# adc.net
KiCad netlist of a schematic drawn in EAGLE
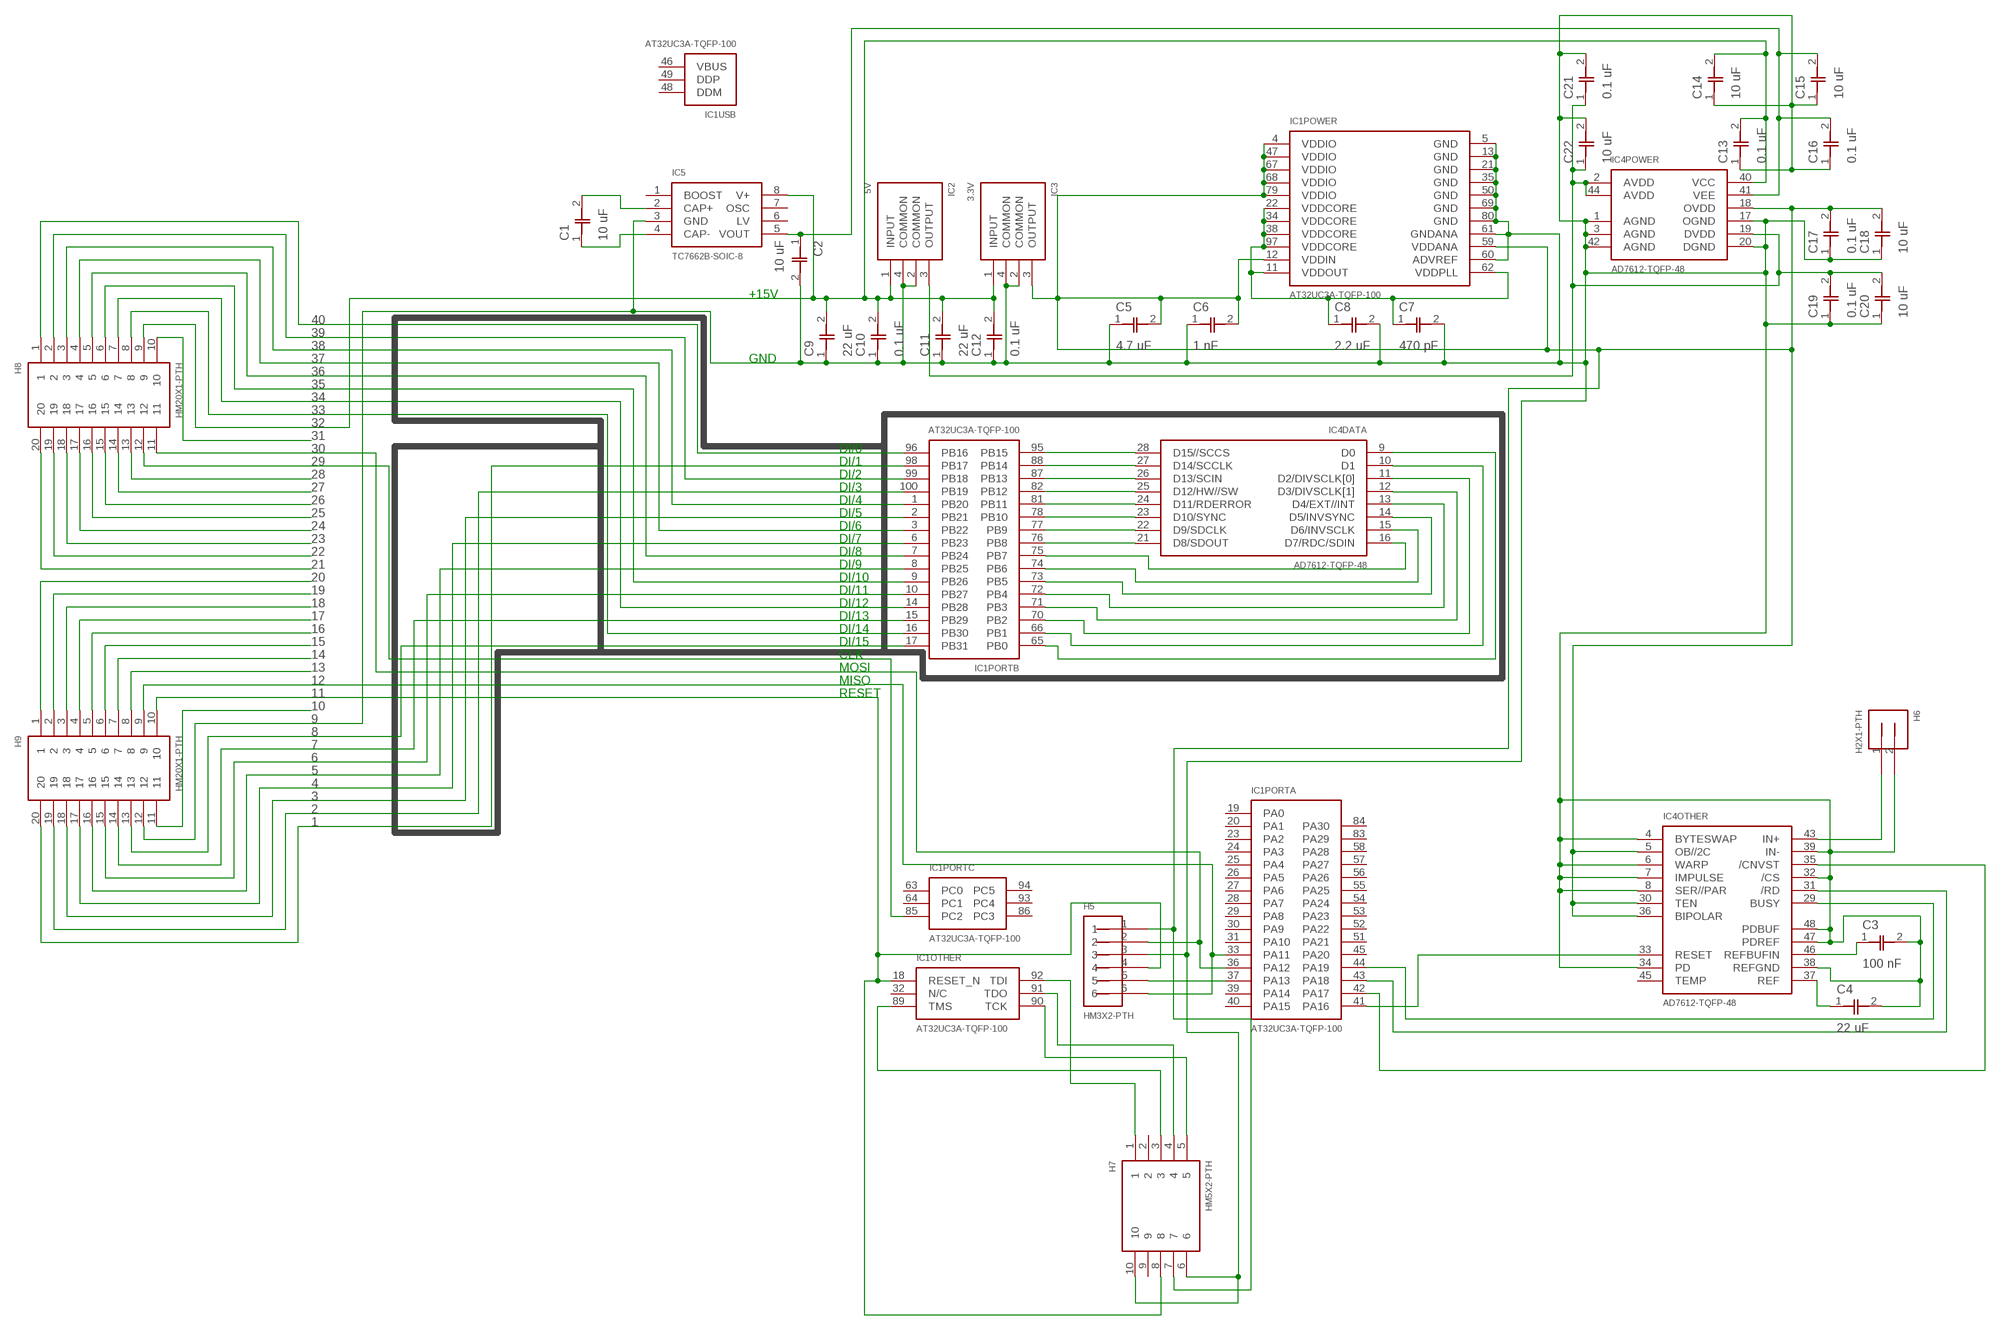
[diagram p0: schematic, sheet 1]

(export (version "E")
  (design (tool "Eeschema 10.0.6"))
  (components
    (comp (ref "C1")
      (value "10 uF")
      (footprint "eagle-import:CAP-0805")
      (libsource (lib "eagle-import") (part "CAP-0805"))
    )
    (comp (ref "C2")
      (value "10 uF")
      (footprint "eagle-import:CAP-0805")
      (libsource (lib "eagle-import") (part "CAP-0805"))
    )
    (comp (ref "C3")
      (value "100 nF")
      (footprint "eagle-import:CAP-0603")
      (libsource (lib "eagle-import") (part "july13b_CAP-0603"))
    )
    (comp (ref "C4")
      (value "22 uF")
      (footprint "eagle-import:CAP-0805")
      (libsource (lib "eagle-import") (part "CAP-0805"))
    )
    (comp (ref "C5")
      (value "4.7 uF")
      (footprint "eagle-import:CAP-0603")
      (libsource (lib "eagle-import") (part "july13b_CAP-0603"))
    )
    (comp (ref "C6")
      (value "1 nF")
      (footprint "eagle-import:CAP-0603")
      (libsource (lib "eagle-import") (part "july13b_CAP-0603"))
    )
    (comp (ref "C7")
      (value "470 pF")
      (footprint "eagle-import:CAP-0603")
      (libsource (lib "eagle-import") (part "july13b_CAP-0603"))
    )
    (comp (ref "C8")
      (value "2.2 uF")
      (footprint "eagle-import:CAP-0603")
      (libsource (lib "eagle-import") (part "july13b_CAP-0603"))
    )
    (comp (ref "C9")
      (value "22 uF")
      (footprint "eagle-import:CAP-0805")
      (libsource (lib "eagle-import") (part "CAP-0805"))
    )
    (comp (ref "C10")
      (value "0.1 uF")
      (footprint "eagle-import:CAP-0603")
      (libsource (lib "eagle-import") (part "july13b_CAP-0603"))
    )
    (comp (ref "C11")
      (value "22 uF")
      (footprint "eagle-import:CAP-0805")
      (libsource (lib "eagle-import") (part "CAP-0805"))
    )
    (comp (ref "C12")
      (value "0.1 uF")
      (footprint "eagle-import:CAP-0603")
      (libsource (lib "eagle-import") (part "july13b_CAP-0603"))
    )
    (comp (ref "C13")
      (value "0.1 uF")
      (footprint "eagle-import:CAP-0603")
      (libsource (lib "eagle-import") (part "july13b_CAP-0603"))
    )
    (comp (ref "C14")
      (value "10 uF")
      (footprint "eagle-import:CAP-0805")
      (libsource (lib "eagle-import") (part "CAP-0805"))
    )
    (comp (ref "C15")
      (value "10 uF")
      (footprint "eagle-import:CAP-0805")
      (libsource (lib "eagle-import") (part "CAP-0805"))
    )
    (comp (ref "C16")
      (value "0.1 uF")
      (footprint "eagle-import:CAP-0603")
      (libsource (lib "eagle-import") (part "july13b_CAP-0603"))
    )
    (comp (ref "C17")
      (value "0.1 uF")
      (footprint "eagle-import:CAP-0603")
      (libsource (lib "eagle-import") (part "july13b_CAP-0603"))
    )
    (comp (ref "C18")
      (value "10 uF")
      (footprint "eagle-import:CAP-0603")
      (libsource (lib "eagle-import") (part "july13b_CAP-0603"))
    )
    (comp (ref "C19")
      (value "0.1 uF")
      (footprint "eagle-import:CAP-0603")
      (libsource (lib "eagle-import") (part "july13b_CAP-0603"))
    )
    (comp (ref "C20")
      (value "10 uF")
      (footprint "eagle-import:CAP-0603")
      (libsource (lib "eagle-import") (part "july13b_CAP-0603"))
    )
    (comp (ref "C21")
      (value "0.1 uF")
      (footprint "eagle-import:CAP-0603")
      (libsource (lib "eagle-import") (part "july13b_CAP-0603"))
    )
    (comp (ref "C22")
      (value "10 uF")
      (footprint "eagle-import:CAP-0603")
      (libsource (lib "eagle-import") (part "july13b_CAP-0603"))
    )
    (comp (ref "H5")
      (value "HM3X2-PTH")
      (footprint "eagle-import:HM3X2-PTH")
      (libsource (lib "eagle-import") (part "HM3X2-PTH"))
    )
    (comp (ref "H6")
      (value "H2X1-PTH")
      (footprint "eagle-import:HM2X1-PTH")
      (libsource (lib "eagle-import") (part "H2X1-PTH"))
    )
    (comp (ref "H7")
      (value "HM5X2-PTH")
      (footprint "eagle-import:HM5X2-PTH")
      (libsource (lib "eagle-import") (part "HM5X2-PTH"))
    )
    (comp (ref "H8")
      (value "HM20X1-PTH")
      (footprint "eagle-import:HM20X1-PTH")
      (libsource (lib "eagle-import") (part "HM20X1-PTH"))
    )
    (comp (ref "H9")
      (value "HM20X1-PTH")
      (footprint "eagle-import:HM20X1-PTH")
      (libsource (lib "eagle-import") (part "HM20X1-PTH"))
    )
    (comp (ref "IC1")
      (value "AT32UC3A-TQFP-100")
      (footprint "eagle-import:TQFP-100")
      (libsource (lib "eagle-import") (part "AT32UC3A-TQFP-100"))
    )
    (comp (ref "IC2")
      (value "5V")
      (footprint "eagle-import:SOT-223-4")
      (libsource (lib "eagle-import") (part "UA78M-SOT-223-4"))
    )
    (comp (ref "IC3")
      (value "3.3V")
      (footprint "eagle-import:SOT-223-4")
      (libsource (lib "eagle-import") (part "UA78M-SOT-223-4"))
    )
    (comp (ref "IC4")
      (value "AD7612-TQFP-48")
      (footprint "eagle-import:LQFP-48")
      (libsource (lib "eagle-import") (part "AD7612-TQFP-48"))
    )
    (comp (ref "IC5")
      (value "TC7662B-SOIC-8")
      (footprint "eagle-import:SOIC-8")
      (libsource (lib "eagle-import") (part "TC7662B-SOIC-8"))
    )
  )
  (nets
    (net (code "1") (name "/1") (class "Default")
      (node (ref "H9") (pin "20") (pinfunction "20_20") (pintype "bidirectional"))
      (node (ref "IC1") (pin "98") (pinfunction "PB17_98") (pintype "bidirectional"))
    )
    (net (code "2") (name "/2") (class "Default")
      (node (ref "H9") (pin "19") (pinfunction "19_19") (pintype "bidirectional"))
      (node (ref "IC1") (pin "100") (pinfunction "PB19_100") (pintype "bidirectional"))
    )
    (net (code "3") (name "/3") (class "Default")
      (node (ref "H9") (pin "18") (pinfunction "18_18") (pintype "bidirectional"))
      (node (ref "IC1") (pin "2") (pinfunction "PB21_2") (pintype "bidirectional"))
    )
    (net (code "4") (name "/4") (class "Default")
      (node (ref "H9") (pin "17") (pinfunction "17_17") (pintype "bidirectional"))
      (node (ref "IC1") (pin "6") (pinfunction "PB23_6") (pintype "bidirectional"))
    )
    (net (code "5") (name "/5") (class "Default")
      (node (ref "H9") (pin "16") (pinfunction "16_16") (pintype "bidirectional"))
      (node (ref "IC1") (pin "8") (pinfunction "PB25_8") (pintype "bidirectional"))
    )
    (net (code "6") (name "/6") (class "Default")
      (node (ref "H9") (pin "15") (pinfunction "15_15") (pintype "bidirectional"))
      (node (ref "IC1") (pin "10") (pinfunction "PB27_10") (pintype "bidirectional"))
    )
    (net (code "7") (name "/7") (class "Default")
      (node (ref "H9") (pin "14") (pinfunction "14_14") (pintype "bidirectional"))
      (node (ref "IC1") (pin "15") (pinfunction "PB29_15") (pintype "bidirectional"))
    )
    (net (code "8") (name "/8") (class "Default")
      (node (ref "H9") (pin "13") (pinfunction "13_13") (pintype "bidirectional"))
      (node (ref "IC1") (pin "17") (pinfunction "PB31_17") (pintype "bidirectional"))
    )
    (net (code "9") (name "/9") (class "Default")
      (node (ref "C10") (pin "1") (pinfunction "1_1") (pintype "passive"))
      (node (ref "C11") (pin "1") (pinfunction "1_1") (pintype "passive"))
      (node (ref "C12") (pin "1") (pinfunction "1_1") (pintype "passive"))
      (node (ref "C13") (pin "1") (pinfunction "1_1") (pintype "passive"))
      (node (ref "C14") (pin "1") (pinfunction "1_1") (pintype "passive"))
      (node (ref "C15") (pin "1") (pinfunction "1_1") (pintype "passive"))
      (node (ref "C16") (pin "1") (pinfunction "1_1") (pintype "passive"))
      (node (ref "C17") (pin "1") (pinfunction "1_1") (pintype "passive"))
      (node (ref "C18") (pin "1") (pinfunction "1_1") (pintype "passive"))
      (node (ref "C19") (pin "1") (pinfunction "1_1") (pintype "passive"))
      (node (ref "C2") (pin "2") (pinfunction "2_2") (pintype "passive"))
      (node (ref "C20") (pin "1") (pinfunction "1_1") (pintype "passive"))
      (node (ref "C21") (pin "2") (pinfunction "2_2") (pintype "passive"))
      (node (ref "C22") (pin "2") (pinfunction "2_2") (pintype "passive"))
      (node (ref "C3") (pin "2") (pinfunction "2_2") (pintype "passive"))
      (node (ref "C4") (pin "2") (pinfunction "2_2") (pintype "passive"))
      (node (ref "C5") (pin "1") (pinfunction "1_1") (pintype "passive"))
      (node (ref "C6") (pin "1") (pinfunction "1_1") (pintype "passive"))
      (node (ref "C7") (pin "2") (pinfunction "2_2") (pintype "passive"))
      (node (ref "C8") (pin "2") (pinfunction "2_2") (pintype "passive"))
      (node (ref "C9") (pin "1") (pinfunction "1_1") (pintype "passive"))
      (node (ref "H5") (pin "3") (pinfunction "3_3") (pintype "passive"))
      (node (ref "H6") (pin "2") (pinfunction "2_2") (pintype "passive"))
      (node (ref "H7") (pin "10") (pinfunction "10_10") (pintype "passive"))
      (node (ref "H7") (pin "6") (pinfunction "6_6") (pintype "passive"))
      (node (ref "H9") (pin "12") (pinfunction "12_12") (pintype "bidirectional"))
      (node (ref "IC1") (pin "13") (pinfunction "GND_13") (pintype "power_in"))
      (node (ref "IC1") (pin "21") (pinfunction "GND_21") (pintype "power_in"))
      (node (ref "IC1") (pin "35") (pinfunction "GND_35") (pintype "power_in"))
      (node (ref "IC1") (pin "5") (pinfunction "GND_5") (pintype "power_in"))
      (node (ref "IC1") (pin "50") (pinfunction "GND_50") (pintype "power_in"))
      (node (ref "IC1") (pin "60") (pinfunction "ADVREF_60") (pintype "bidirectional"))
      (node (ref "IC1") (pin "61") (pinfunction "GNDANA_61") (pintype "power_in"))
      (node (ref "IC1") (pin "69") (pinfunction "GND_69") (pintype "power_in"))
      (node (ref "IC1") (pin "80") (pinfunction "GND_80") (pintype "power_in"))
      (node (ref "IC2") (pin "2") (pinfunction "COMMON_2") (pintype "power_in"))
      (node (ref "IC2") (pin "4") (pinfunction "COMMON_4") (pintype "power_in"))
      (node (ref "IC3") (pin "2") (pinfunction "COMMON_2") (pintype "power_in"))
      (node (ref "IC3") (pin "4") (pinfunction "COMMON_4") (pintype "power_in"))
      (node (ref "IC4") (pin "1") (pinfunction "AGND_1") (pintype "power_in"))
      (node (ref "IC4") (pin "17") (pinfunction "OGND_17") (pintype "power_in"))
      (node (ref "IC4") (pin "20") (pinfunction "DGND_20") (pintype "power_in"))
      (node (ref "IC4") (pin "3") (pinfunction "AGND_3") (pintype "power_in"))
      (node (ref "IC4") (pin "32") (pinfunction "/CS_32") (pintype "input"))
      (node (ref "IC4") (pin "34") (pinfunction "PD_34") (pintype "input"))
      (node (ref "IC4") (pin "38") (pinfunction "REFGND_38") (pintype "input"))
      (node (ref "IC4") (pin "39") (pinfunction "IN-_39") (pintype "input"))
      (node (ref "IC4") (pin "4") (pinfunction "BYTESWAP_4") (pintype "input"))
      (node (ref "IC4") (pin "42") (pinfunction "AGND_42") (pintype "power_in"))
      (node (ref "IC4") (pin "47") (pinfunction "PDREF_47") (pintype "input"))
      (node (ref "IC4") (pin "48") (pinfunction "PDBUF_48") (pintype "input"))
      (node (ref "IC4") (pin "6") (pinfunction "WARP_6") (pintype "input"))
      (node (ref "IC4") (pin "7") (pinfunction "IMPULSE_7") (pintype "input"))
      (node (ref "IC4") (pin "8") (pinfunction "SER//PAR_8") (pintype "input"))
      (node (ref "IC5") (pin "3") (pinfunction "GND_3") (pintype "power_in"))
    )
    (net (code "10") (name "/10") (class "Default")
      (node (ref "H9") (pin "11") (pinfunction "11_11") (pintype "bidirectional"))
    )
    (net (code "11") (name "/11") (class "Default")
      (node (ref "H5") (pin "4") (pinfunction "4_4") (pintype "passive"))
      (node (ref "H7") (pin "8") (pinfunction "8_8") (pintype "passive"))
      (node (ref "H9") (pin "10") (pinfunction "10_10") (pintype "bidirectional"))
      (node (ref "IC1") (pin "18") (pinfunction "RESET_N_18") (pintype "bidirectional"))
    )
    (net (code "12") (name "/12") (class "Default")
      (node (ref "H5") (pin "6") (pinfunction "6_6") (pintype "passive"))
      (node (ref "H9") (pin "9") (pinfunction "9_9") (pintype "bidirectional"))
      (node (ref "IC1") (pin "33") (pinfunction "PA11_33") (pintype "bidirectional"))
    )
    (net (code "13") (name "/13") (class "Default")
      (node (ref "H9") (pin "8") (pinfunction "8_8") (pintype "bidirectional"))
    )
    (net (code "14") (name "/14") (class "Default")
      (node (ref "H9") (pin "7") (pinfunction "7_7") (pintype "bidirectional"))
    )
    (net (code "15") (name "/15") (class "Default")
      (node (ref "H9") (pin "6") (pinfunction "6_6") (pintype "bidirectional"))
    )
    (net (code "16") (name "/16") (class "Default")
      (node (ref "H9") (pin "5") (pinfunction "5_5") (pintype "bidirectional"))
    )
    (net (code "17") (name "/17") (class "Default")
      (node (ref "H9") (pin "4") (pinfunction "4_4") (pintype "bidirectional"))
    )
    (net (code "18") (name "/18") (class "Default")
      (node (ref "H9") (pin "3") (pinfunction "3_3") (pintype "bidirectional"))
    )
    (net (code "19") (name "/19") (class "Default")
      (node (ref "H9") (pin "2") (pinfunction "2_2") (pintype "bidirectional"))
    )
    (net (code "20") (name "/20") (class "Default")
      (node (ref "H9") (pin "1") (pinfunction "1_1") (pintype "bidirectional"))
    )
    (net (code "21") (name "/21") (class "Default")
      (node (ref "H8") (pin "20") (pinfunction "20_20") (pintype "bidirectional"))
    )
    (net (code "22") (name "/22") (class "Default")
      (node (ref "H8") (pin "19") (pinfunction "19_19") (pintype "bidirectional"))
    )
    (net (code "23") (name "/23") (class "Default")
      (node (ref "H8") (pin "18") (pinfunction "18_18") (pintype "bidirectional"))
    )
    (net (code "24") (name "/24") (class "Default")
      (node (ref "H8") (pin "17") (pinfunction "17_17") (pintype "bidirectional"))
    )
    (net (code "25") (name "/25") (class "Default")
      (node (ref "H8") (pin "16") (pinfunction "16_16") (pintype "bidirectional"))
    )
    (net (code "26") (name "/26") (class "Default")
      (node (ref "H8") (pin "15") (pinfunction "15_15") (pintype "bidirectional"))
    )
    (net (code "27") (name "/27") (class "Default")
      (node (ref "H8") (pin "14") (pinfunction "14_14") (pintype "bidirectional"))
    )
    (net (code "28") (name "/28") (class "Default")
      (node (ref "H8") (pin "13") (pinfunction "13_13") (pintype "bidirectional"))
    )
    (net (code "29") (name "/29") (class "Default")
      (node (ref "H8") (pin "12") (pinfunction "12_12") (pintype "bidirectional"))
      (node (ref "IC1") (pin "85") (pinfunction "PC2_85") (pintype "bidirectional"))
    )
    (net (code "30") (name "/30") (class "Default")
      (node (ref "H5") (pin "2") (pinfunction "2_2") (pintype "passive"))
      (node (ref "H8") (pin "11") (pinfunction "11_11") (pintype "bidirectional"))
      (node (ref "IC1") (pin "36") (pinfunction "PA12_36") (pintype "bidirectional"))
    )
    (net (code "31") (name "/31") (class "Default")
      (node (ref "H8") (pin "10") (pinfunction "10_10") (pintype "bidirectional"))
    )
    (net (code "32") (name "/32") (class "Default")
      (node (ref "C10") (pin "2") (pinfunction "2_2") (pintype "passive"))
      (node (ref "C11") (pin "2") (pinfunction "2_2") (pintype "passive"))
      (node (ref "C12") (pin "2") (pinfunction "2_2") (pintype "passive"))
      (node (ref "C13") (pin "2") (pinfunction "2_2") (pintype "passive"))
      (node (ref "C14") (pin "2") (pinfunction "2_2") (pintype "passive"))
      (node (ref "C9") (pin "2") (pinfunction "2_2") (pintype "passive"))
      (node (ref "H8") (pin "9") (pinfunction "9_9") (pintype "bidirectional"))
      (node (ref "IC2") (pin "1") (pinfunction "INPUT_1") (pintype "power_in"))
      (node (ref "IC3") (pin "1") (pinfunction "INPUT_1") (pintype "power_in"))
      (node (ref "IC4") (pin "40") (pinfunction "VCC_40") (pintype "power_in"))
      (node (ref "IC5") (pin "8") (pinfunction "V+_8") (pintype "power_in"))
    )
    (net (code "33") (name "/33") (class "Default")
      (node (ref "H8") (pin "8") (pinfunction "8_8") (pintype "bidirectional"))
      (node (ref "IC1") (pin "16") (pinfunction "PB30_16") (pintype "bidirectional"))
    )
    (net (code "34") (name "/34") (class "Default")
      (node (ref "H8") (pin "7") (pinfunction "7_7") (pintype "bidirectional"))
      (node (ref "IC1") (pin "14") (pinfunction "PB28_14") (pintype "bidirectional"))
    )
    (net (code "35") (name "/35") (class "Default")
      (node (ref "H8") (pin "6") (pinfunction "6_6") (pintype "bidirectional"))
      (node (ref "IC1") (pin "9") (pinfunction "PB26_9") (pintype "bidirectional"))
    )
    (net (code "36") (name "/36") (class "Default")
      (node (ref "H8") (pin "5") (pinfunction "5_5") (pintype "bidirectional"))
      (node (ref "IC1") (pin "7") (pinfunction "PB24_7") (pintype "bidirectional"))
    )
    (net (code "37") (name "/37") (class "Default")
      (node (ref "H8") (pin "4") (pinfunction "4_4") (pintype "bidirectional"))
      (node (ref "IC1") (pin "3") (pinfunction "PB22_3") (pintype "bidirectional"))
    )
    (net (code "38") (name "/38") (class "Default")
      (node (ref "H8") (pin "3") (pinfunction "3_3") (pintype "bidirectional"))
      (node (ref "IC1") (pin "1") (pinfunction "PB20_1") (pintype "bidirectional"))
    )
    (net (code "39") (name "/39") (class "Default")
      (node (ref "H8") (pin "2") (pinfunction "2_2") (pintype "bidirectional"))
      (node (ref "IC1") (pin "99") (pinfunction "PB18_99") (pintype "bidirectional"))
    )
    (net (code "40") (name "/40") (class "Default")
      (node (ref "H8") (pin "1") (pinfunction "1_1") (pintype "bidirectional"))
      (node (ref "IC1") (pin "96") (pinfunction "PB16_96") (pintype "bidirectional"))
    )
    (net (code "41") (name "Net-(IC1A-TCK)") (class "Default")
      (node (ref "H7") (pin "5") (pinfunction "5_5") (pintype "passive"))
      (node (ref "IC1") (pin "90") (pinfunction "TCK_90") (pintype "bidirectional"))
    )
    (net (code "42") (name "Net-(IC1A-TDI)") (class "Default")
      (node (ref "H7") (pin "1") (pinfunction "1_1") (pintype "passive"))
      (node (ref "IC1") (pin "92") (pinfunction "TDI_92") (pintype "bidirectional"))
    )
    (net (code "43") (name "Net-(IC1A-TDO)") (class "Default")
      (node (ref "H7") (pin "4") (pinfunction "4_4") (pintype "passive"))
      (node (ref "IC1") (pin "91") (pinfunction "TDO_91") (pintype "bidirectional"))
    )
    (net (code "44") (name "Net-(IC1A-TMS)") (class "Default")
      (node (ref "H7") (pin "3") (pinfunction "3_3") (pintype "passive"))
      (node (ref "IC1") (pin "89") (pinfunction "TMS_89") (pintype "bidirectional"))
    )
    (net (code "45") (name "Net-(IC1B-PA13)") (class "Default")
      (node (ref "H5") (pin "5") (pinfunction "5_5") (pintype "passive"))
      (node (ref "IC1") (pin "37") (pinfunction "PA13_37") (pintype "bidirectional"))
    )
    (net (code "46") (name "Net-(IC1B-PA16)") (class "Default")
      (node (ref "IC1") (pin "41") (pinfunction "PA16_41") (pintype "bidirectional"))
      (node (ref "IC4") (pin "33") (pinfunction "RESET_33") (pintype "input"))
    )
    (net (code "47") (name "Net-(IC1B-PA17)") (class "Default")
      (node (ref "IC1") (pin "42") (pinfunction "PA17_42") (pintype "bidirectional"))
      (node (ref "IC4") (pin "35") (pinfunction "/CNVST_35") (pintype "input"))
    )
    (net (code "48") (name "Net-(IC1B-PA18)") (class "Default")
      (node (ref "IC1") (pin "43") (pinfunction "PA18_43") (pintype "bidirectional"))
      (node (ref "IC4") (pin "31") (pinfunction "/RD_31") (pintype "input"))
    )
    (net (code "49") (name "Net-(IC1B-PA19)") (class "Default")
      (node (ref "IC1") (pin "44") (pinfunction "PA19_44") (pintype "bidirectional"))
      (node (ref "IC4") (pin "29") (pinfunction "BUSY_29") (pintype "output"))
    )
    (net (code "50") (name "Net-(IC1C-PB0)") (class "Default")
      (node (ref "IC1") (pin "65") (pinfunction "PB0_65") (pintype "bidirectional"))
      (node (ref "IC4") (pin "9") (pinfunction "D0_9") (pintype "output"))
    )
    (net (code "51") (name "Net-(IC1C-PB1)") (class "Default")
      (node (ref "IC1") (pin "66") (pinfunction "PB1_66") (pintype "bidirectional"))
      (node (ref "IC4") (pin "10") (pinfunction "D1_10") (pintype "output"))
    )
    (net (code "52") (name "Net-(IC1C-PB2)") (class "Default")
      (node (ref "IC1") (pin "70") (pinfunction "PB2_70") (pintype "bidirectional"))
      (node (ref "IC4") (pin "11") (pinfunction "D2/DIVSCLK[0]_11") (pintype "bidirectional"))
    )
    (net (code "53") (name "Net-(IC1C-PB3)") (class "Default")
      (node (ref "IC1") (pin "71") (pinfunction "PB3_71") (pintype "bidirectional"))
      (node (ref "IC4") (pin "12") (pinfunction "D3/DIVSCLK[1]_12") (pintype "bidirectional"))
    )
    (net (code "54") (name "Net-(IC1C-PB4)") (class "Default")
      (node (ref "IC1") (pin "72") (pinfunction "PB4_72") (pintype "bidirectional"))
      (node (ref "IC4") (pin "13") (pinfunction "D4/EXT//INT_13") (pintype "bidirectional"))
    )
    (net (code "55") (name "Net-(IC1C-PB5)") (class "Default")
      (node (ref "IC1") (pin "73") (pinfunction "PB5_73") (pintype "bidirectional"))
      (node (ref "IC4") (pin "14") (pinfunction "D5/INVSYNC_14") (pintype "bidirectional"))
    )
    (net (code "56") (name "Net-(IC1C-PB6)") (class "Default")
      (node (ref "IC1") (pin "74") (pinfunction "PB6_74") (pintype "bidirectional"))
      (node (ref "IC4") (pin "15") (pinfunction "D6/INVSCLK_15") (pintype "bidirectional"))
    )
    (net (code "57") (name "Net-(IC1C-PB7)") (class "Default")
      (node (ref "IC1") (pin "75") (pinfunction "PB7_75") (pintype "bidirectional"))
      (node (ref "IC4") (pin "16") (pinfunction "D7/RDC/SDIN_16") (pintype "bidirectional"))
    )
    (net (code "58") (name "Net-(IC1C-PB8)") (class "Default")
      (node (ref "IC1") (pin "76") (pinfunction "PB8_76") (pintype "bidirectional"))
      (node (ref "IC4") (pin "21") (pinfunction "D8/SDOUT_21") (pintype "output"))
    )
    (net (code "59") (name "Net-(IC1C-PB9)") (class "Default")
      (node (ref "IC1") (pin "77") (pinfunction "PB9_77") (pintype "bidirectional"))
      (node (ref "IC4") (pin "22") (pinfunction "D9/SDCLK_22") (pintype "bidirectional"))
    )
    (net (code "60") (name "Net-(IC1C-PB10)") (class "Default")
      (node (ref "IC1") (pin "78") (pinfunction "PB10_78") (pintype "bidirectional"))
      (node (ref "IC4") (pin "23") (pinfunction "D10/SYNC_23") (pintype "output"))
    )
    (net (code "61") (name "Net-(IC1C-PB11)") (class "Default")
      (node (ref "IC1") (pin "81") (pinfunction "PB11_81") (pintype "bidirectional"))
      (node (ref "IC4") (pin "24") (pinfunction "D11/RDERROR_24") (pintype "output"))
    )
    (net (code "62") (name "Net-(IC1C-PB12)") (class "Default")
      (node (ref "IC1") (pin "82") (pinfunction "PB12_82") (pintype "bidirectional"))
      (node (ref "IC4") (pin "25") (pinfunction "D12/HW//SW_25") (pintype "bidirectional"))
    )
    (net (code "63") (name "Net-(IC1C-PB13)") (class "Default")
      (node (ref "IC1") (pin "87") (pinfunction "PB13_87") (pintype "bidirectional"))
      (node (ref "IC4") (pin "26") (pinfunction "D13/SCIN_26") (pintype "bidirectional"))
    )
    (net (code "64") (name "Net-(IC1C-PB14)") (class "Default")
      (node (ref "IC1") (pin "88") (pinfunction "PB14_88") (pintype "bidirectional"))
      (node (ref "IC4") (pin "27") (pinfunction "D14/SCCLK_27") (pintype "bidirectional"))
    )
    (net (code "65") (name "Net-(IC1C-PB15)") (class "Default")
      (node (ref "IC1") (pin "95") (pinfunction "PB15_95") (pintype "bidirectional"))
      (node (ref "IC4") (pin "28") (pinfunction "D15//SCCS_28") (pintype "bidirectional"))
    )
    (net (code "66") (name "Net-(IC1E-VDDANA)") (class "Default")
      (node (ref "C17") (pin "2") (pinfunction "2_2") (pintype "passive"))
      (node (ref "C18") (pin "2") (pinfunction "2_2") (pintype "passive"))
      (node (ref "C5") (pin "2") (pinfunction "2_2") (pintype "passive"))
      (node (ref "C6") (pin "2") (pinfunction "2_2") (pintype "passive"))
      (node (ref "H5") (pin "1") (pinfunction "1_1") (pintype "passive"))
      (node (ref "H7") (pin "7") (pinfunction "7_7") (pintype "passive"))
      (node (ref "IC1") (pin "12") (pinfunction "VDDIN_12") (pintype "input"))
      (node (ref "IC1") (pin "4") (pinfunction "VDDIO_4") (pintype "bidirectional"))
      (node (ref "IC1") (pin "47") (pinfunction "VDDIO_47") (pintype "bidirectional"))
      (node (ref "IC1") (pin "59") (pinfunction "VDDANA_59") (pintype "bidirectional"))
      (node (ref "IC1") (pin "67") (pinfunction "VDDIO_67") (pintype "bidirectional"))
      (node (ref "IC1") (pin "68") (pinfunction "VDDIO_68") (pintype "bidirectional"))
      (node (ref "IC1") (pin "79") (pinfunction "VDDIO_79") (pintype "bidirectional"))
      (node (ref "IC3") (pin "3") (pinfunction "OUTPUT_3") (pintype "power_in"))
      (node (ref "IC4") (pin "18") (pinfunction "OVDD_18") (pintype "power_in"))
      (node (ref "IC4") (pin "30") (pinfunction "TEN_30") (pintype "input"))
      (node (ref "IC4") (pin "36") (pinfunction "BIPOLAR_36") (pintype "input"))
      (node (ref "IC4") (pin "5") (pinfunction "OB//2C_5") (pintype "input"))
    )
    (net (code "67") (name "Net-(IC1E-VDDOUT)") (class "Default")
      (node (ref "C7") (pin "1") (pinfunction "1_1") (pintype "passive"))
      (node (ref "C8") (pin "1") (pinfunction "1_1") (pintype "passive"))
      (node (ref "IC1") (pin "11") (pinfunction "VDDOUT_11") (pintype "output"))
      (node (ref "IC1") (pin "22") (pinfunction "VDDCORE_22") (pintype "bidirectional"))
      (node (ref "IC1") (pin "34") (pinfunction "VDDCORE_34") (pintype "bidirectional"))
      (node (ref "IC1") (pin "38") (pinfunction "VDDCORE_38") (pintype "bidirectional"))
      (node (ref "IC1") (pin "62") (pinfunction "VDDPLL_62") (pintype "bidirectional"))
      (node (ref "IC1") (pin "97") (pinfunction "VDDCORE_97") (pintype "bidirectional"))
    )
    (net (code "68") (name "Net-(IC2-OUTPUT)") (class "Default")
      (node (ref "C19") (pin "2") (pinfunction "2_2") (pintype "passive"))
      (node (ref "C20") (pin "2") (pinfunction "2_2") (pintype "passive"))
      (node (ref "C21") (pin "1") (pinfunction "1_1") (pintype "passive"))
      (node (ref "C22") (pin "1") (pinfunction "1_1") (pintype "passive"))
      (node (ref "IC2") (pin "3") (pinfunction "OUTPUT_3") (pintype "power_in"))
      (node (ref "IC4") (pin "19") (pinfunction "DVDD_19") (pintype "power_in"))
      (node (ref "IC4") (pin "2") (pinfunction "AVDD_2") (pintype "power_in"))
      (node (ref "IC4") (pin "44") (pinfunction "AVDD_44") (pintype "power_in"))
    )
    (net (code "69") (name "Net-(IC4B-IN+)") (class "Default")
      (node (ref "H6") (pin "1") (pinfunction "1_1") (pintype "passive"))
      (node (ref "IC4") (pin "43") (pinfunction "IN+_43") (pintype "input"))
    )
    (net (code "70") (name "Net-(IC4B-REF)") (class "Default")
      (node (ref "C4") (pin "1") (pinfunction "1_1") (pintype "passive"))
      (node (ref "IC4") (pin "37") (pinfunction "REF_37") (pintype "bidirectional"))
    )
    (net (code "71") (name "Net-(IC4B-REFBUFIN)") (class "Default")
      (node (ref "C3") (pin "1") (pinfunction "1_1") (pintype "passive"))
      (node (ref "IC4") (pin "46") (pinfunction "REFBUFIN_46") (pintype "input"))
    )
    (net (code "72") (name "Net-(IC4C-VEE)") (class "Default")
      (node (ref "C15") (pin "2") (pinfunction "2_2") (pintype "passive"))
      (node (ref "C16") (pin "2") (pinfunction "2_2") (pintype "passive"))
      (node (ref "C2") (pin "1") (pinfunction "1_1") (pintype "passive"))
      (node (ref "IC4") (pin "41") (pinfunction "VEE_41") (pintype "power_in"))
      (node (ref "IC5") (pin "5") (pinfunction "VOUT_5") (pintype "power_in"))
    )
    (net (code "73") (name "Net-(IC5-CAP+)") (class "Default")
      (node (ref "C1") (pin "2") (pinfunction "2_2") (pintype "passive"))
      (node (ref "IC5") (pin "2") (pinfunction "CAP+_2") (pintype "passive"))
    )
    (net (code "74") (name "Net-(IC5-CAP-)") (class "Default")
      (node (ref "C1") (pin "1") (pinfunction "1_1") (pintype "passive"))
      (node (ref "IC5") (pin "4") (pinfunction "CAP-_4") (pintype "passive"))
    )
    (net (code "75") (name "unconnected-(H7-Pad2)") (class "Default")
      (node (ref "H7") (pin "2") (pinfunction "2_2") (pintype "passive"))
    )
    (net (code "76") (name "unconnected-(H7-Pad9)") (class "Default")
      (node (ref "H7") (pin "9") (pinfunction "9_9") (pintype "passive"))
    )
    (net (code "77") (name "unconnected-(IC1A-N{slash}C-Pad32)") (class "Default")
      (node (ref "IC1") (pin "32") (pinfunction "N/C_32") (pintype "no_connect"))
    )
    (net (code "78") (name "unconnected-(IC1B-PA0-Pad19)") (class "Default")
      (node (ref "IC1") (pin "19") (pinfunction "PA0_19") (pintype "bidirectional"))
    )
    (net (code "79") (name "unconnected-(IC1B-PA1-Pad20)") (class "Default")
      (node (ref "IC1") (pin "20") (pinfunction "PA1_20") (pintype "bidirectional"))
    )
    (net (code "80") (name "unconnected-(IC1B-PA2-Pad23)") (class "Default")
      (node (ref "IC1") (pin "23") (pinfunction "PA2_23") (pintype "bidirectional"))
    )
    (net (code "81") (name "unconnected-(IC1B-PA3-Pad24)") (class "Default")
      (node (ref "IC1") (pin "24") (pinfunction "PA3_24") (pintype "bidirectional"))
    )
    (net (code "82") (name "unconnected-(IC1B-PA4-Pad25)") (class "Default")
      (node (ref "IC1") (pin "25") (pinfunction "PA4_25") (pintype "bidirectional"))
    )
    (net (code "83") (name "unconnected-(IC1B-PA5-Pad26)") (class "Default")
      (node (ref "IC1") (pin "26") (pinfunction "PA5_26") (pintype "bidirectional"))
    )
    (net (code "84") (name "unconnected-(IC1B-PA6-Pad27)") (class "Default")
      (node (ref "IC1") (pin "27") (pinfunction "PA6_27") (pintype "bidirectional"))
    )
    (net (code "85") (name "unconnected-(IC1B-PA7-Pad28)") (class "Default")
      (node (ref "IC1") (pin "28") (pinfunction "PA7_28") (pintype "bidirectional"))
    )
    (net (code "86") (name "unconnected-(IC1B-PA8-Pad29)") (class "Default")
      (node (ref "IC1") (pin "29") (pinfunction "PA8_29") (pintype "bidirectional"))
    )
    (net (code "87") (name "unconnected-(IC1B-PA9-Pad30)") (class "Default")
      (node (ref "IC1") (pin "30") (pinfunction "PA9_30") (pintype "bidirectional"))
    )
    (net (code "88") (name "unconnected-(IC1B-PA10-Pad31)") (class "Default")
      (node (ref "IC1") (pin "31") (pinfunction "PA10_31") (pintype "bidirectional"))
    )
    (net (code "89") (name "unconnected-(IC1B-PA14-Pad39)") (class "Default")
      (node (ref "IC1") (pin "39") (pinfunction "PA14_39") (pintype "bidirectional"))
    )
    (net (code "90") (name "unconnected-(IC1B-PA15-Pad40)") (class "Default")
      (node (ref "IC1") (pin "40") (pinfunction "PA15_40") (pintype "bidirectional"))
    )
    (net (code "91") (name "unconnected-(IC1B-PA20-Pad45)") (class "Default")
      (node (ref "IC1") (pin "45") (pinfunction "PA20_45") (pintype "bidirectional"))
    )
    (net (code "92") (name "unconnected-(IC1B-PA21-Pad51)") (class "Default")
      (node (ref "IC1") (pin "51") (pinfunction "PA21_51") (pintype "bidirectional"))
    )
    (net (code "93") (name "unconnected-(IC1B-PA22-Pad52)") (class "Default")
      (node (ref "IC1") (pin "52") (pinfunction "PA22_52") (pintype "bidirectional"))
    )
    (net (code "94") (name "unconnected-(IC1B-PA23-Pad53)") (class "Default")
      (node (ref "IC1") (pin "53") (pinfunction "PA23_53") (pintype "bidirectional"))
    )
    (net (code "95") (name "unconnected-(IC1B-PA24-Pad54)") (class "Default")
      (node (ref "IC1") (pin "54") (pinfunction "PA24_54") (pintype "bidirectional"))
    )
    (net (code "96") (name "unconnected-(IC1B-PA25-Pad55)") (class "Default")
      (node (ref "IC1") (pin "55") (pinfunction "PA25_55") (pintype "bidirectional"))
    )
    (net (code "97") (name "unconnected-(IC1B-PA26-Pad56)") (class "Default")
      (node (ref "IC1") (pin "56") (pinfunction "PA26_56") (pintype "bidirectional"))
    )
    (net (code "98") (name "unconnected-(IC1B-PA27-Pad57)") (class "Default")
      (node (ref "IC1") (pin "57") (pinfunction "PA27_57") (pintype "bidirectional"))
    )
    (net (code "99") (name "unconnected-(IC1B-PA28-Pad58)") (class "Default")
      (node (ref "IC1") (pin "58") (pinfunction "PA28_58") (pintype "bidirectional"))
    )
    (net (code "100") (name "unconnected-(IC1B-PA29-Pad83)") (class "Default")
      (node (ref "IC1") (pin "83") (pinfunction "PA29_83") (pintype "bidirectional"))
    )
    (net (code "101") (name "unconnected-(IC1B-PA30-Pad84)") (class "Default")
      (node (ref "IC1") (pin "84") (pinfunction "PA30_84") (pintype "bidirectional"))
    )
    (net (code "102") (name "unconnected-(IC1D-PC0-Pad63)") (class "Default")
      (node (ref "IC1") (pin "63") (pinfunction "PC0_63") (pintype "bidirectional"))
    )
    (net (code "103") (name "unconnected-(IC1D-PC1-Pad64)") (class "Default")
      (node (ref "IC1") (pin "64") (pinfunction "PC1_64") (pintype "bidirectional"))
    )
    (net (code "104") (name "unconnected-(IC1D-PC3-Pad86)") (class "Default")
      (node (ref "IC1") (pin "86") (pinfunction "PC3_86") (pintype "bidirectional"))
    )
    (net (code "105") (name "unconnected-(IC1D-PC4-Pad93)") (class "Default")
      (node (ref "IC1") (pin "93") (pinfunction "PC4_93") (pintype "bidirectional"))
    )
    (net (code "106") (name "unconnected-(IC1D-PC5-Pad94)") (class "Default")
      (node (ref "IC1") (pin "94") (pinfunction "PC5_94") (pintype "bidirectional"))
    )
    (net (code "107") (name "unconnected-(IC1F-DDM-Pad48)") (class "Default")
      (node (ref "IC1") (pin "48") (pinfunction "DDM_48") (pintype "bidirectional"))
    )
    (net (code "108") (name "unconnected-(IC1F-DDP-Pad49)") (class "Default")
      (node (ref "IC1") (pin "49") (pinfunction "DDP_49") (pintype "bidirectional"))
    )
    (net (code "109") (name "unconnected-(IC1F-VBUS-Pad46)") (class "Default")
      (node (ref "IC1") (pin "46") (pinfunction "VBUS_46") (pintype "bidirectional"))
    )
    (net (code "110") (name "unconnected-(IC4B-TEMP-Pad45)") (class "Default")
      (node (ref "IC4") (pin "45") (pinfunction "TEMP_45") (pintype "output"))
    )
    (net (code "111") (name "unconnected-(IC5-BOOST-Pad1)") (class "Default")
      (node (ref "IC5") (pin "1") (pinfunction "BOOST_1") (pintype "input"))
    )
    (net (code "112") (name "unconnected-(IC5-LV-Pad6)") (class "Default")
      (node (ref "IC5") (pin "6") (pinfunction "LV_6") (pintype "input"))
    )
    (net (code "113") (name "unconnected-(IC5-OSC-Pad7)") (class "Default")
      (node (ref "IC5") (pin "7") (pinfunction "OSC_7") (pintype "passive"))
    )
  )
)
